# CON_PCIe_X4.net
KiCad netlist of a schematic drawn in Altium Designer
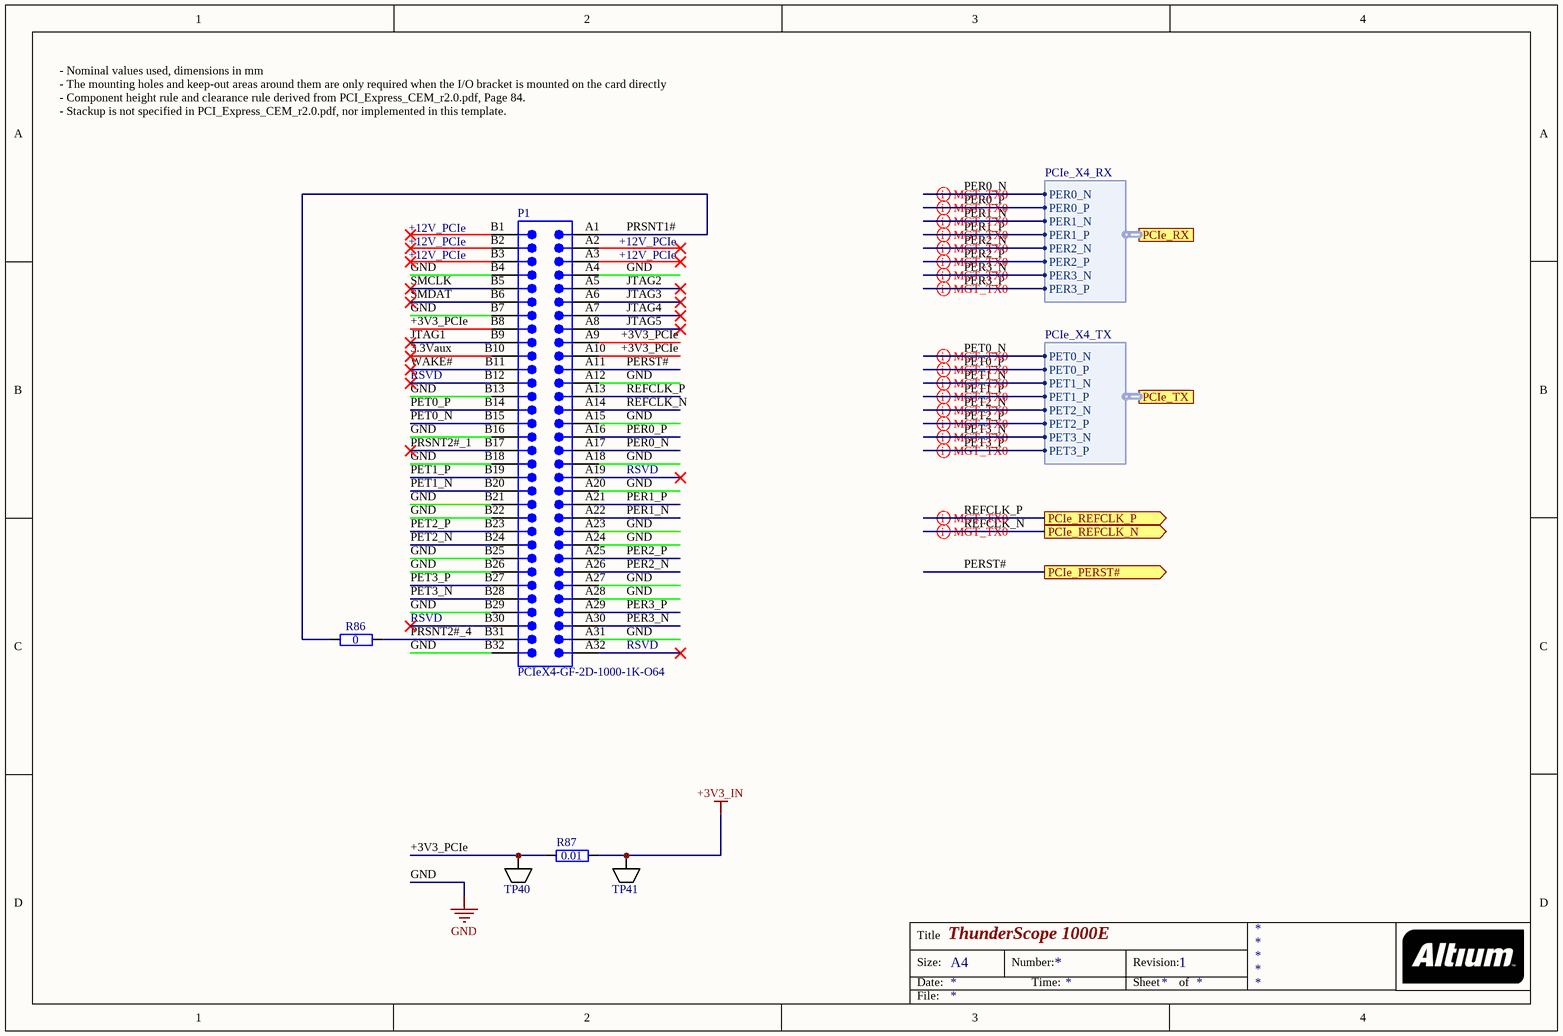
[diagram p0: CON_PCIe_X4.SchDoc]

(export (version "E")
  (design (tool "Eeschema 10.0.6"))
  (components
    (comp (ref "P1")
      (value "PCIeX4-GF-2D-1000-1K-O64")
      (footprint "PCIeX4-GF-2D-1000-1K-O64")
      (description "Golden finger, PCIeX4, Dual, Opposite, Pitch 1mm, 64-Position")
      (fields (field (name "PUBLISHER") "Altium"))
      (libsource (lib "Altium Content Vault") (part "PCIeX4-GF-2D-1000-1K-O64"))
    )
    (comp (ref "R86")
      (value "0")
      (footprint "GEN_R_0402")
      (libsource (lib "DSO") (part "RES 0 OHM 1/16W 0402"))
    )
    (comp (ref "R87")
      (value "0.01")
      (footprint "GEN_R_0603")
      (fields (field (name "TOLERANCE") "1%"))
      (libsource (lib "DSO") (part "RES 0.01 OHM 1% 1/4W 0603"))
    )
    (comp (ref "TP40")
      (value "5015")
      (footprint "KEY_5015")
      (libsource (lib "DSO") (part "TP KEYSTONE 5015"))
    )
    (comp (ref "TP41")
      (value "5015")
      (footprint "KEY_5015")
      (libsource (lib "DSO") (part "TP KEYSTONE 5015"))
    )
  )
  (nets
    (net (code "3") (name "+3V3_IN") (class "Default")
      (node (ref "R87") (pin "2") (pinfunction "2_2") (pintype "passive"))
      (node (ref "TP41") (pin "1") (pinfunction "1_1") (pintype "passive"))
    )
    (net (code "4") (name "/+3V3_PCIe") (class "Default")
      (node (ref "P1") (pin "A10") (pinfunction "A10_A10") (pintype "passive"))
      (node (ref "P1") (pin "A9") (pinfunction "A9_A9") (pintype "passive"))
      (node (ref "P1") (pin "B8") (pinfunction "B8_B8") (pintype "passive"))
      (node (ref "R87") (pin "1") (pinfunction "1_1") (pintype "passive"))
      (node (ref "TP40") (pin "1") (pinfunction "1_1") (pintype "passive"))
    )
    (net (code "5") (name "/3.3Vaux") (class "Default")
      (node (ref "P1") (pin "B10") (pinfunction "B10_B10") (pintype "passive+no_connect"))
    )
    (net (code "6") (name "/JTAG1") (class "Default")
      (node (ref "P1") (pin "B9") (pinfunction "B9_B9") (pintype "passive+no_connect"))
    )
    (net (code "7") (name "/JTAG2") (class "Default")
      (node (ref "P1") (pin "A5") (pinfunction "A5_A5") (pintype "passive+no_connect"))
    )
    (net (code "8") (name "/JTAG3") (class "Default")
      (node (ref "P1") (pin "A6") (pinfunction "A6_A6") (pintype "passive+no_connect"))
    )
    (net (code "9") (name "/JTAG4") (class "Default")
      (node (ref "P1") (pin "A7") (pinfunction "A7_A7") (pintype "passive+no_connect"))
    )
    (net (code "10") (name "/JTAG5") (class "Default")
      (node (ref "P1") (pin "A8") (pinfunction "A8_A8") (pintype "passive+no_connect"))
    )
    (net (code "11") (name "/PER0_N") (class "Default")
      (node (ref "P1") (pin "A17") (pinfunction "A17_A17") (pintype "passive"))
    )
    (net (code "12") (name "/PER0_P") (class "Default")
      (node (ref "P1") (pin "A16") (pinfunction "A16_A16") (pintype "passive"))
    )
    (net (code "13") (name "/PER1_N") (class "Default")
      (node (ref "P1") (pin "A22") (pinfunction "A22_A22") (pintype "passive"))
    )
    (net (code "14") (name "/PER1_P") (class "Default")
      (node (ref "P1") (pin "A21") (pinfunction "A21_A21") (pintype "passive"))
    )
    (net (code "15") (name "/PER2_N") (class "Default")
      (node (ref "P1") (pin "A26") (pinfunction "A26_A26") (pintype "passive"))
    )
    (net (code "16") (name "/PER2_P") (class "Default")
      (node (ref "P1") (pin "A25") (pinfunction "A25_A25") (pintype "passive"))
    )
    (net (code "17") (name "/PER3_N") (class "Default")
      (node (ref "P1") (pin "A30") (pinfunction "A30_A30") (pintype "passive"))
    )
    (net (code "18") (name "/PER3_P") (class "Default")
      (node (ref "P1") (pin "A29") (pinfunction "A29_A29") (pintype "passive"))
    )
    (net (code "19") (name "/PERST#") (class "Default")
      (node (ref "P1") (pin "A11") (pinfunction "A11_A11") (pintype "passive"))
    )
    (net (code "20") (name "/PET0_N") (class "Default")
      (node (ref "P1") (pin "B15") (pinfunction "B15_B15") (pintype "passive"))
    )
    (net (code "21") (name "/PET0_P") (class "Default")
      (node (ref "P1") (pin "B14") (pinfunction "B14_B14") (pintype "passive"))
    )
    (net (code "22") (name "/PET1_N") (class "Default")
      (node (ref "P1") (pin "B20") (pinfunction "B20_B20") (pintype "passive"))
    )
    (net (code "23") (name "/PET1_P") (class "Default")
      (node (ref "P1") (pin "B19") (pinfunction "B19_B19") (pintype "passive"))
    )
    (net (code "24") (name "/PET2_N") (class "Default")
      (node (ref "P1") (pin "B24") (pinfunction "B24_B24") (pintype "passive"))
    )
    (net (code "25") (name "/PET2_P") (class "Default")
      (node (ref "P1") (pin "B23") (pinfunction "B23_B23") (pintype "passive"))
    )
    (net (code "26") (name "/PET3_N") (class "Default")
      (node (ref "P1") (pin "B28") (pinfunction "B28_B28") (pintype "passive"))
    )
    (net (code "27") (name "/PET3_P") (class "Default")
      (node (ref "P1") (pin "B27") (pinfunction "B27_B27") (pintype "passive"))
    )
    (net (code "28") (name "/PRSNT1#") (class "Default")
      (node (ref "P1") (pin "A1") (pinfunction "A1_A1") (pintype "passive"))
      (node (ref "R86") (pin "1") (pinfunction "1_1") (pintype "passive"))
    )
    (net (code "29") (name "/PRSNT2#_1") (class "Default")
      (node (ref "P1") (pin "B17") (pinfunction "B17_B17") (pintype "passive+no_connect"))
    )
    (net (code "30") (name "/PRSNT2#_4") (class "Default")
      (node (ref "P1") (pin "B31") (pinfunction "B31_B31") (pintype "passive"))
      (node (ref "R86") (pin "2") (pinfunction "2_2") (pintype "passive"))
    )
    (net (code "31") (name "/REFCLK_N") (class "Default")
      (node (ref "P1") (pin "A14") (pinfunction "A14_A14") (pintype "passive"))
    )
    (net (code "32") (name "/REFCLK_P") (class "Default")
      (node (ref "P1") (pin "A13") (pinfunction "A13_A13") (pintype "passive"))
    )
    (net (code "33") (name "/SMCLK") (class "Default")
      (node (ref "P1") (pin "B5") (pinfunction "B5_B5") (pintype "passive+no_connect"))
    )
    (net (code "34") (name "/SMDAT") (class "Default")
      (node (ref "P1") (pin "B6") (pinfunction "B6_B6") (pintype "passive+no_connect"))
    )
    (net (code "35") (name "/WAKE#") (class "Default")
      (node (ref "P1") (pin "B11") (pinfunction "B11_B11") (pintype "passive+no_connect"))
    )
    (net (code "38") (name "GND") (class "Default")
      (node (ref "P1") (pin "A12") (pinfunction "A12_A12") (pintype "passive"))
      (node (ref "P1") (pin "A15") (pinfunction "A15_A15") (pintype "passive"))
      (node (ref "P1") (pin "A18") (pinfunction "A18_A18") (pintype "passive"))
      (node (ref "P1") (pin "A20") (pinfunction "A20_A20") (pintype "passive"))
      (node (ref "P1") (pin "A23") (pinfunction "A23_A23") (pintype "passive"))
      (node (ref "P1") (pin "A24") (pinfunction "A24_A24") (pintype "passive"))
      (node (ref "P1") (pin "A27") (pinfunction "A27_A27") (pintype "passive"))
      (node (ref "P1") (pin "A28") (pinfunction "A28_A28") (pintype "passive"))
      (node (ref "P1") (pin "A31") (pinfunction "A31_A31") (pintype "passive"))
      (node (ref "P1") (pin "A4") (pinfunction "A4_A4") (pintype "passive"))
      (node (ref "P1") (pin "B13") (pinfunction "B13_B13") (pintype "passive"))
      (node (ref "P1") (pin "B16") (pinfunction "B16_B16") (pintype "passive"))
      (node (ref "P1") (pin "B18") (pinfunction "B18_B18") (pintype "passive"))
      (node (ref "P1") (pin "B21") (pinfunction "B21_B21") (pintype "passive"))
      (node (ref "P1") (pin "B22") (pinfunction "B22_B22") (pintype "passive"))
      (node (ref "P1") (pin "B25") (pinfunction "B25_B25") (pintype "passive"))
      (node (ref "P1") (pin "B26") (pinfunction "B26_B26") (pintype "passive"))
      (node (ref "P1") (pin "B29") (pinfunction "B29_B29") (pintype "passive"))
      (node (ref "P1") (pin "B32") (pinfunction "B32_B32") (pintype "passive"))
      (node (ref "P1") (pin "B4") (pinfunction "B4_B4") (pintype "passive"))
      (node (ref "P1") (pin "B7") (pinfunction "B7_B7") (pintype "passive"))
    )
    (net (code "39") (name "unconnected-(P1-PadA2)") (class "Default")
      (node (ref "P1") (pin "A2") (pinfunction "A2_A2") (pintype "passive+no_connect"))
    )
    (net (code "40") (name "unconnected-(P1-PadA3)") (class "Default")
      (node (ref "P1") (pin "A3") (pinfunction "A3_A3") (pintype "passive+no_connect"))
    )
    (net (code "41") (name "unconnected-(P1-PadA19)") (class "Default")
      (node (ref "P1") (pin "A19") (pinfunction "A19_A19") (pintype "passive+no_connect"))
    )
    (net (code "42") (name "unconnected-(P1-PadA32)") (class "Default")
      (node (ref "P1") (pin "A32") (pinfunction "A32_A32") (pintype "passive+no_connect"))
    )
    (net (code "43") (name "unconnected-(P1-PadB1)") (class "Default")
      (node (ref "P1") (pin "B1") (pinfunction "B1_B1") (pintype "passive+no_connect"))
    )
    (net (code "44") (name "unconnected-(P1-PadB2)") (class "Default")
      (node (ref "P1") (pin "B2") (pinfunction "B2_B2") (pintype "passive+no_connect"))
    )
    (net (code "45") (name "unconnected-(P1-PadB3)") (class "Default")
      (node (ref "P1") (pin "B3") (pinfunction "B3_B3") (pintype "passive+no_connect"))
    )
    (net (code "46") (name "unconnected-(P1-PadB12)") (class "Default")
      (node (ref "P1") (pin "B12") (pinfunction "B12_B12") (pintype "passive+no_connect"))
    )
    (net (code "47") (name "unconnected-(P1-PadB30)") (class "Default")
      (node (ref "P1") (pin "B30") (pinfunction "B30_B30") (pintype "passive+no_connect"))
    )
  )
)
